# Sheet1.net
KiCad netlist of a schematic drawn in Altium Designer
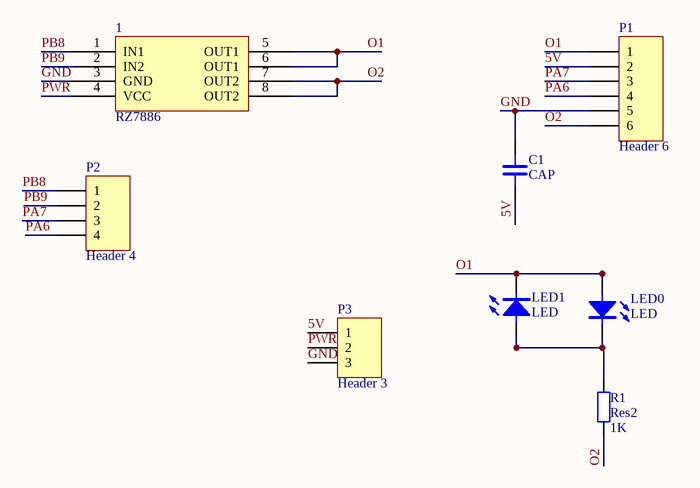
[diagram p0: Sheet1.SchDoc]

(export (version "E")
  (design (tool "Eeschema 10.0.6"))
  (components
    (comp (ref "1")
      (value "RZ7886")
      (footprint "RZ7886 - duplicate")
      (libsource (lib "Schlib1") (part "RZ7886"))
    )
    (comp (ref "C1")
      (value "CAP")
      (footprint "0805")
      (description "Capacitor")
      (libsource (lib "General") (part "CAP"))
    )
    (comp (ref "LED0") (value "LED") (footprint "LED-0805") (libsource (lib "General") (part "LED")))
    (comp (ref "LED1") (value "LED") (footprint "LED-0805") (libsource (lib "General") (part "LED")))
    (comp (ref "P1")
      (value "Header 6")
      (footprint "HDR1X6")
      (description "Header, 6-Pin")
      (fields (field (name "PUBLISHER") "Altium Limited"))
      (libsource (lib "Miscellaneous Connectors") (part "Header 6"))
    )
    (comp (ref "P2")
      (value "Header 4")
      (footprint "HDR1X4")
      (description "Header, 4-Pin")
      (fields (field (name "PUBLISHER") "Altium Limited"))
      (libsource (lib "Miscellaneous Connectors") (part "Header 4"))
    )
    (comp (ref "P3")
      (value "Header 3")
      (footprint "HDR1X3")
      (description "Header, 3-Pin")
      (fields (field (name "PUBLISHER") "Altium Limited"))
      (libsource (lib "Miscellaneous Connectors") (part "Header 3"))
    )
    (comp (ref "R1")
      (value "Res2")
      (footprint "AXIAL-0.4")
      (description "Resistor")
      (fields (field (name "ALTIUM_VALUE") "1K") (field (name "PUBLISHER") "Altium Limited"))
      (libsource (lib "Miscellaneous Devices") (part "Res2"))
    )
  )
  (nets
    (net (code "1") (name "/5V") (class "Default")
      (node (ref "C1") (pin "1") (pinfunction "1_1") (pintype "passive"))
      (node (ref "P1") (pin "2") (pinfunction "2_2") (pintype "passive"))
      (node (ref "P3") (pin "1") (pinfunction "1_1") (pintype "passive"))
    )
    (net (code "2") (name "/GND") (class "Default")
      (node (ref "1") (pin "3") (pinfunction "GND_3") (pintype "passive"))
      (node (ref "C1") (pin "2") (pinfunction "2_2") (pintype "passive"))
      (node (ref "P1") (pin "5") (pinfunction "5_5") (pintype "passive"))
      (node (ref "P3") (pin "3") (pinfunction "3_3") (pintype "passive"))
    )
    (net (code "3") (name "/O1") (class "Default")
      (node (ref "1") (pin "5") (pinfunction "OUT1_5") (pintype "passive"))
      (node (ref "1") (pin "6") (pinfunction "OUT1_6") (pintype "passive"))
      (node (ref "LED0") (pin "1") (pinfunction "A_1") (pintype "passive"))
      (node (ref "LED1") (pin "2") (pinfunction "C_2") (pintype "passive"))
      (node (ref "P1") (pin "1") (pinfunction "1_1") (pintype "passive"))
    )
    (net (code "4") (name "/O2") (class "Default")
      (node (ref "1") (pin "7") (pinfunction "OUT2_7") (pintype "passive"))
      (node (ref "1") (pin "8") (pinfunction "OUT2_8") (pintype "passive"))
      (node (ref "P1") (pin "6") (pinfunction "6_6") (pintype "passive"))
      (node (ref "R1") (pin "1") (pinfunction "1_1") (pintype "passive"))
    )
    (net (code "5") (name "/PA6") (class "Default")
      (node (ref "P1") (pin "4") (pinfunction "4_4") (pintype "passive"))
      (node (ref "P2") (pin "4") (pinfunction "4_4") (pintype "passive"))
    )
    (net (code "6") (name "/PA7") (class "Default")
      (node (ref "P1") (pin "3") (pinfunction "3_3") (pintype "passive"))
      (node (ref "P2") (pin "3") (pinfunction "3_3") (pintype "passive"))
    )
    (net (code "7") (name "/PB8") (class "Default")
      (node (ref "1") (pin "1") (pinfunction "IN1_1") (pintype "passive"))
      (node (ref "P2") (pin "1") (pinfunction "1_1") (pintype "passive"))
    )
    (net (code "8") (name "/PB9") (class "Default")
      (node (ref "1") (pin "2") (pinfunction "IN2_2") (pintype "passive"))
      (node (ref "P2") (pin "2") (pinfunction "2_2") (pintype "passive"))
    )
    (net (code "9") (name "/PWR") (class "Default")
      (node (ref "1") (pin "4") (pinfunction "VCC_4") (pintype "passive"))
      (node (ref "P3") (pin "2") (pinfunction "2_2") (pintype "passive"))
    )
    (net (code "10") (name "Net-(LED0-C)") (class "Default")
      (node (ref "LED0") (pin "2") (pinfunction "C_2") (pintype "passive"))
      (node (ref "LED1") (pin "1") (pinfunction "A_1") (pintype "passive"))
      (node (ref "R1") (pin "2") (pinfunction "2_2") (pintype "passive"))
    )
  )
)
